# COUNTER1.net
KiCad netlist of a schematic drawn in EAGLE
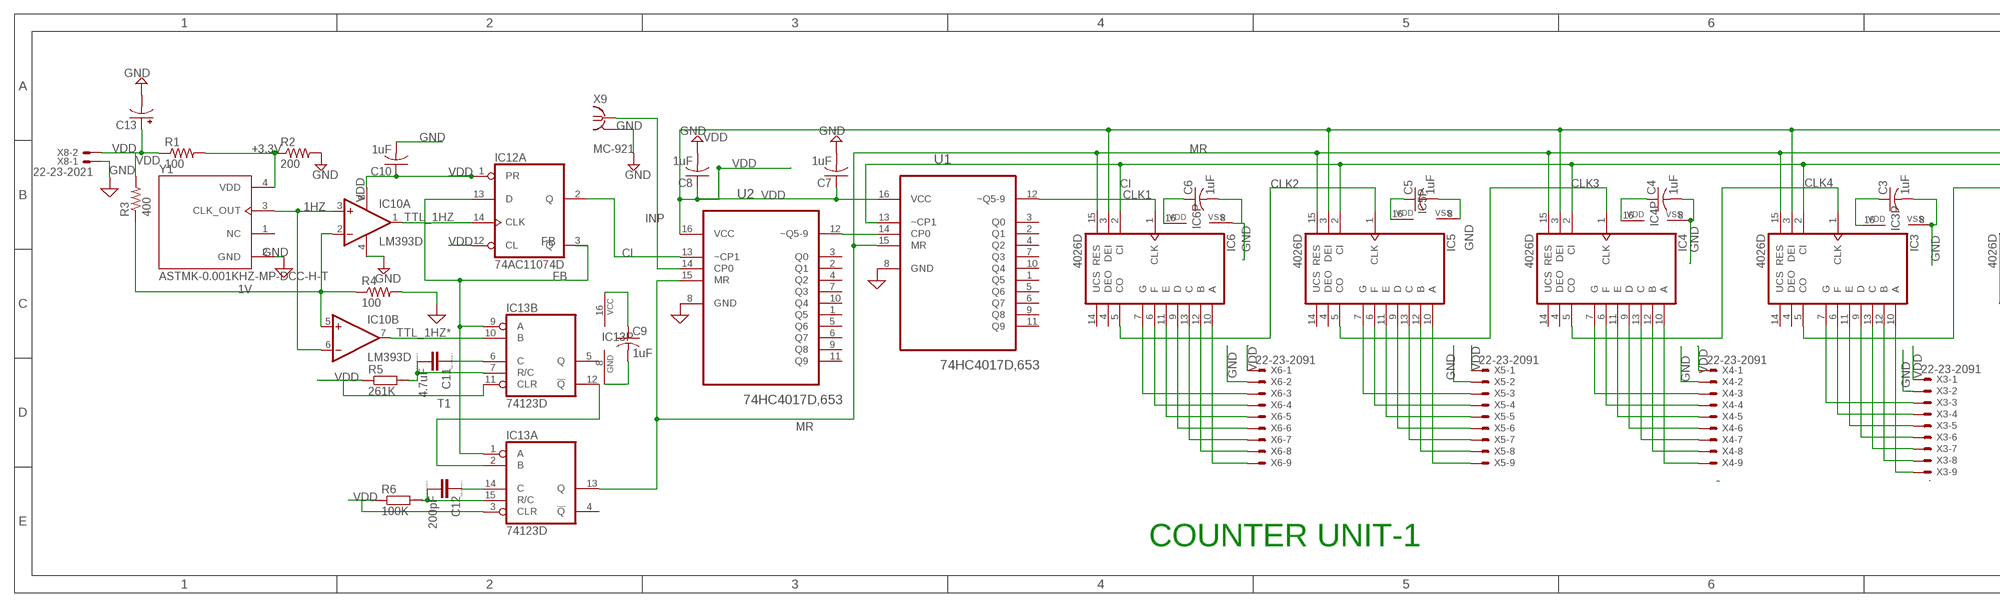
[diagram p0: schematic, sheet 1, part 1 of 2]
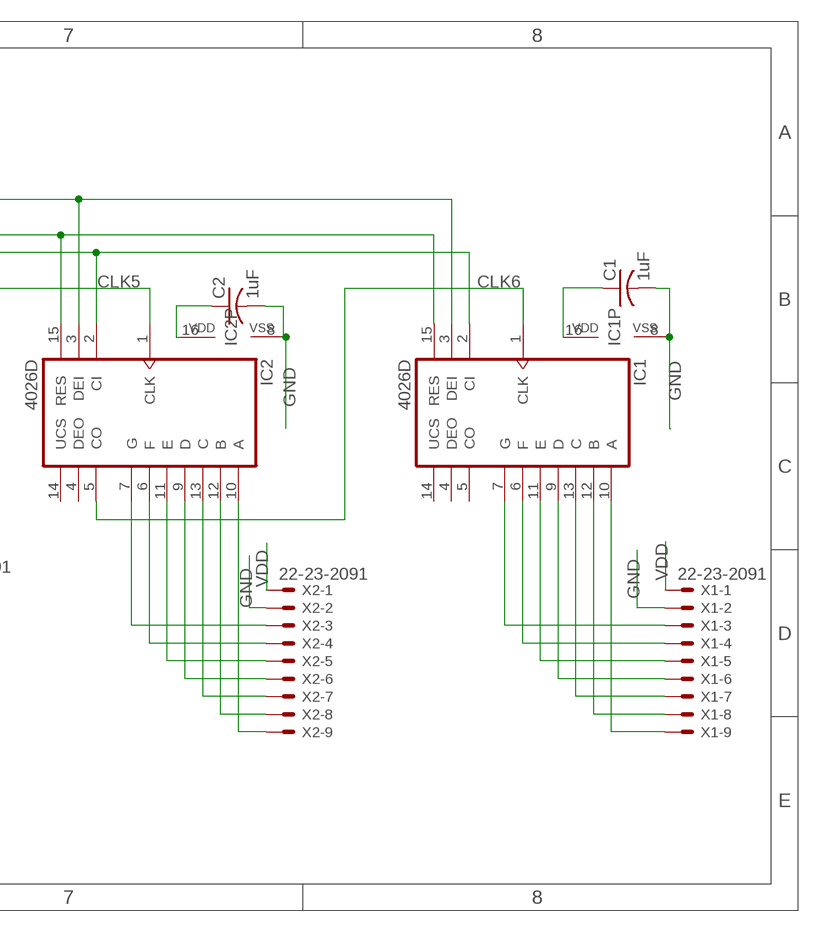
[diagram p1: schematic, sheet 1, part 2 of 2]

(export (version "E")
  (design (tool "Eeschema 10.0.6"))
  (components
    (comp (ref "C1")
      (value "1uF")
      (footprint "eagle-import:C0603")
      (libsource (lib "eagle-import") (part "C-USC0603"))
    )
    (comp (ref "C2")
      (value "1uF")
      (footprint "eagle-import:C0603")
      (libsource (lib "eagle-import") (part "C-USC0603"))
    )
    (comp (ref "C3")
      (value "1uF")
      (footprint "eagle-import:C0603")
      (libsource (lib "eagle-import") (part "C-USC0603"))
    )
    (comp (ref "C4")
      (value "1uF")
      (footprint "eagle-import:C0603")
      (libsource (lib "eagle-import") (part "C-USC0603"))
    )
    (comp (ref "C5")
      (value "1uF")
      (footprint "eagle-import:C0603")
      (libsource (lib "eagle-import") (part "C-USC0603"))
    )
    (comp (ref "C6")
      (value "1uF")
      (footprint "eagle-import:C0603")
      (libsource (lib "eagle-import") (part "C-USC0603"))
    )
    (comp (ref "C7")
      (value "1uF")
      (footprint "eagle-import:C0603")
      (libsource (lib "eagle-import") (part "C-USC0603"))
    )
    (comp (ref "C8")
      (value "1uF")
      (footprint "eagle-import:C0603")
      (libsource (lib "eagle-import") (part "C-USC0603"))
    )
    (comp (ref "C9")
      (value "1uF")
      (footprint "eagle-import:C0603")
      (libsource (lib "eagle-import") (part "C-USC0603"))
    )
    (comp (ref "C10")
      (value "1uF")
      (footprint "eagle-import:C0603")
      (libsource (lib "eagle-import") (part "C-USC0603"))
    )
    (comp (ref "C11")
      (value "4.7uF")
      (footprint "eagle-import:C0603")
      (libsource (lib "eagle-import") (part "CC0603"))
    )
    (comp (ref "C12")
      (value "200pF")
      (footprint "eagle-import:C0603")
      (libsource (lib "eagle-import") (part "CC0603"))
    )
    (comp (ref "C13")
      (value "CPOL-USE2-5")
      (footprint "eagle-import:E2-5")
      (libsource (lib "eagle-import") (part "CPOL-USE2-5"))
    )
    (comp (ref "IC1")
      (value "4026D")
      (footprint "eagle-import:SO16")
      (libsource (lib "eagle-import") (part "4026D"))
    )
    (comp (ref "IC2")
      (value "4026D")
      (footprint "eagle-import:SO16")
      (libsource (lib "eagle-import") (part "4026D"))
    )
    (comp (ref "IC3")
      (value "4026D")
      (footprint "eagle-import:SO16")
      (libsource (lib "eagle-import") (part "4026D"))
    )
    (comp (ref "IC4")
      (value "4026D")
      (footprint "eagle-import:SO16")
      (libsource (lib "eagle-import") (part "4026D"))
    )
    (comp (ref "IC5")
      (value "4026D")
      (footprint "eagle-import:SO16")
      (libsource (lib "eagle-import") (part "4026D"))
    )
    (comp (ref "IC6")
      (value "4026D")
      (footprint "eagle-import:SO16")
      (libsource (lib "eagle-import") (part "4026D"))
    )
    (comp (ref "IC10")
      (value "LM393D")
      (footprint "eagle-import:SO08")
      (libsource (lib "eagle-import") (part "LM393D"))
    )
    (comp (ref "IC12")
      (value "74AC11074D")
      (footprint "eagle-import:SO14")
      (libsource (lib "eagle-import") (part "74AC11074D"))
    )
    (comp (ref "IC13")
      (value "74123D")
      (footprint "eagle-import:SO16")
      (libsource (lib "eagle-import") (part "74123D"))
    )
    (comp (ref "R1")
      (value "100")
      (footprint "eagle-import:R0603")
      (libsource (lib "eagle-import") (part "R-US_R0603"))
    )
    (comp (ref "R2")
      (value "200")
      (footprint "eagle-import:R0603")
      (libsource (lib "eagle-import") (part "R-US_R0603"))
    )
    (comp (ref "R3")
      (value "400")
      (footprint "eagle-import:R0603")
      (libsource (lib "eagle-import") (part "R-US_R0603"))
    )
    (comp (ref "R4")
      (value "100")
      (footprint "eagle-import:R0603")
      (libsource (lib "eagle-import") (part "R-US_R0603"))
    )
    (comp (ref "R5")
      (value "261K")
      (footprint "eagle-import:R0603")
      (libsource (lib "eagle-import") (part "RR0603"))
    )
    (comp (ref "R6")
      (value "100K")
      (footprint "eagle-import:R0603")
      (libsource (lib "eagle-import") (part "RR0603"))
    )
    (comp (ref "U1")
      (value "74HC4017D,653")
      (footprint "eagle-import:SOIC127P600X175-16N")
      (fields (field (name "MF") "Nexperia USA Inc."))
      (libsource (lib "eagle-import") (part "74HC4017D,653"))
    )
    (comp (ref "U2")
      (value "74HC4017D,653")
      (footprint "eagle-import:SOIC127P600X175-16N")
      (fields (field (name "MF") "Nexperia USA Inc."))
      (libsource (lib "eagle-import") (part "74HC4017D,653"))
    )
    (comp (ref "X1")
      (value "22-23-2091")
      (footprint "eagle-import:22-23-2091")
      (fields (field (name "MF") "MOLEX"))
      (libsource (lib "eagle-import") (part "22-23-2091"))
    )
    (comp (ref "X2")
      (value "22-23-2091")
      (footprint "eagle-import:22-23-2091")
      (fields (field (name "MF") "MOLEX"))
      (libsource (lib "eagle-import") (part "22-23-2091"))
    )
    (comp (ref "X3")
      (value "22-23-2091")
      (footprint "eagle-import:22-23-2091")
      (fields (field (name "MF") "MOLEX"))
      (libsource (lib "eagle-import") (part "22-23-2091"))
    )
    (comp (ref "X4")
      (value "22-23-2091")
      (footprint "eagle-import:22-23-2091")
      (fields (field (name "MF") "MOLEX"))
      (libsource (lib "eagle-import") (part "22-23-2091"))
    )
    (comp (ref "X5")
      (value "22-23-2091")
      (footprint "eagle-import:22-23-2091")
      (fields (field (name "MF") "MOLEX"))
      (libsource (lib "eagle-import") (part "22-23-2091"))
    )
    (comp (ref "X6")
      (value "22-23-2091")
      (footprint "eagle-import:22-23-2091")
      (fields (field (name "MF") "MOLEX"))
      (libsource (lib "eagle-import") (part "22-23-2091"))
    )
    (comp (ref "X8")
      (value "22-23-2021")
      (footprint "eagle-import:22-23-2021")
      (fields (field (name "MF") "MOLEX"))
      (libsource (lib "eagle-import") (part "22-23-2021"))
    )
    (comp (ref "X9")
      (value "MC-921")
      (footprint "eagle-import:MC-921")
      (libsource (lib "eagle-import") (part "MC-921"))
    )
    (comp (ref "Y1")
      (value "ASTMK-0.001KHZ-MP-DCC-H-T")
      (footprint "eagle-import:OSC_ASTMK-0.001KHZ-MP-DCC-H-T")
      (fields (field (name "MF") "Abracon"))
      (libsource (lib "eagle-import") (part "ASTMK-0.001KHZ-MP-DCC-H-T"))
    )
  )
  (nets
    (net (code "1") (name "/+3.3V") (class "Default")
      (node (ref "R1") (pin "2") (pinfunction "2_2") (pintype "passive"))
      (node (ref "R2") (pin "1") (pinfunction "1_1") (pintype "passive"))
      (node (ref "Y1") (pin "4") (pinfunction "VDD_4") (pintype "power_in"))
    )
    (net (code "2") (name "/1HZ") (class "Default")
      (node (ref "IC10") (pin "3") (pinfunction "+IN_3") (pintype "input"))
      (node (ref "IC10") (pin "6") (pinfunction "-IN_6") (pintype "input"))
      (node (ref "Y1") (pin "3") (pinfunction "CLK_OUT_3") (pintype "output"))
    )
    (net (code "3") (name "/1V") (class "Default")
      (node (ref "IC10") (pin "2") (pinfunction "-IN_2") (pintype "input"))
      (node (ref "IC10") (pin "5") (pinfunction "+IN_5") (pintype "input"))
      (node (ref "R3") (pin "1") (pinfunction "1_1") (pintype "passive"))
      (node (ref "R4") (pin "1") (pinfunction "1_1") (pintype "passive"))
    )
    (net (code "4") (name "/CI") (class "Default")
      (node (ref "IC1") (pin "2") (pinfunction "CI_2") (pintype "input"))
      (node (ref "IC12") (pin "2") (pinfunction "Q_2") (pintype "output"))
      (node (ref "IC2") (pin "2") (pinfunction "CI_2") (pintype "input"))
      (node (ref "IC3") (pin "2") (pinfunction "CI_2") (pintype "input"))
      (node (ref "IC4") (pin "2") (pinfunction "CI_2") (pintype "input"))
      (node (ref "IC5") (pin "2") (pinfunction "CI_2") (pintype "input"))
      (node (ref "IC6") (pin "2") (pinfunction "CI_2") (pintype "input"))
      (node (ref "U1") (pin "13") (pinfunction "~{CP1}_13") (pintype "input"))
      (node (ref "U2") (pin "13") (pinfunction "~{CP1}_13") (pintype "input"))
    )
    (net (code "5") (name "/CLK1") (class "Default")
      (node (ref "IC6") (pin "1") (pinfunction "CLK_1") (pintype "input"))
      (node (ref "U1") (pin "12") (pinfunction "~{Q5-9}_12") (pintype "output"))
    )
    (net (code "6") (name "/CLK2") (class "Default")
      (node (ref "IC5") (pin "1") (pinfunction "CLK_1") (pintype "input"))
      (node (ref "IC6") (pin "5") (pinfunction "CO_5") (pintype "output"))
    )
    (net (code "7") (name "/CLK3") (class "Default")
      (node (ref "IC4") (pin "1") (pinfunction "CLK_1") (pintype "input"))
      (node (ref "IC5") (pin "5") (pinfunction "CO_5") (pintype "output"))
    )
    (net (code "8") (name "/CLK4") (class "Default")
      (node (ref "IC3") (pin "1") (pinfunction "CLK_1") (pintype "input"))
      (node (ref "IC4") (pin "5") (pinfunction "CO_5") (pintype "output"))
    )
    (net (code "9") (name "/CLK5") (class "Default")
      (node (ref "IC2") (pin "1") (pinfunction "CLK_1") (pintype "input"))
      (node (ref "IC3") (pin "5") (pinfunction "CO_5") (pintype "output"))
    )
    (net (code "10") (name "/CLK6") (class "Default")
      (node (ref "IC1") (pin "1") (pinfunction "CLK_1") (pintype "input"))
      (node (ref "IC2") (pin "5") (pinfunction "CO_5") (pintype "output"))
    )
    (net (code "11") (name "/FB") (class "Default")
      (node (ref "IC12") (pin "13") (pinfunction "D_13") (pintype "input"))
      (node (ref "IC12") (pin "3") (pinfunction "~{Q}_3") (pintype "output"))
      (node (ref "IC13") (pin "1") (pinfunction "A_1") (pintype "input"))
      (node (ref "IC13") (pin "9") (pinfunction "A_9") (pintype "input"))
    )
    (net (code "12") (name "/INP") (class "Default")
      (node (ref "U2") (pin "14") (pinfunction "CP0_14") (pintype "input"))
      (node (ref "X9") (pin "1") (pinfunction "1_1") (pintype "passive"))
    )
    (net (code "13") (name "/MR") (class "Default")
      (node (ref "IC1") (pin "15") (pinfunction "RES_15") (pintype "input"))
      (node (ref "IC13") (pin "13") (pinfunction "Q_13") (pintype "output"))
      (node (ref "IC2") (pin "15") (pinfunction "RES_15") (pintype "input"))
      (node (ref "IC3") (pin "15") (pinfunction "RES_15") (pintype "input"))
      (node (ref "IC4") (pin "15") (pinfunction "RES_15") (pintype "input"))
      (node (ref "IC5") (pin "15") (pinfunction "RES_15") (pintype "input"))
      (node (ref "IC6") (pin "15") (pinfunction "RES_15") (pintype "input"))
      (node (ref "U1") (pin "15") (pinfunction "MR_15") (pintype "input"))
      (node (ref "U2") (pin "15") (pinfunction "MR_15") (pintype "input"))
    )
    (net (code "14") (name "/RC1") (class "Default")
      (node (ref "C11") (pin "2") (pinfunction "2_2") (pintype "passive"))
      (node (ref "IC13") (pin "7") (pinfunction "R/C_7") (pintype "input"))
      (node (ref "R5") (pin "2") (pinfunction "2_2") (pintype "passive"))
    )
    (net (code "15") (name "/T1") (class "Default")
      (node (ref "IC13") (pin "12") (pinfunction "~{Q}_12") (pintype "output"))
      (node (ref "IC13") (pin "2") (pinfunction "B_2") (pintype "input"))
    )
    (net (code "16") (name "/TTL_1HZ") (class "Default")
      (node (ref "IC10") (pin "1") (pinfunction "OUT_1") (pintype "output"))
      (node (ref "IC12") (pin "14") (pinfunction "CLK_14") (pintype "input"))
    )
    (net (code "17") (name "/TTL_1HZ*") (class "Default")
      (node (ref "IC10") (pin "7") (pinfunction "OUT_7") (pintype "output"))
      (node (ref "IC13") (pin "10") (pinfunction "B_10") (pintype "input"))
    )
    (net (code "18") (name "/VDD") (class "Default")
      (node (ref "C1") (pin "1") (pinfunction "1_1") (pintype "passive"))
      (node (ref "C10") (pin "1") (pinfunction "1_1") (pintype "passive"))
      (node (ref "C13") (pin "+") (pinfunction "+_+") (pintype "passive"))
      (node (ref "C2") (pin "1") (pinfunction "1_1") (pintype "passive"))
      (node (ref "C3") (pin "1") (pinfunction "1_1") (pintype "passive"))
      (node (ref "C4") (pin "1") (pinfunction "1_1") (pintype "passive"))
      (node (ref "C5") (pin "1") (pinfunction "1_1") (pintype "passive"))
      (node (ref "C6") (pin "1") (pinfunction "1_1") (pintype "passive"))
      (node (ref "C7") (pin "1") (pinfunction "1_1") (pintype "passive"))
      (node (ref "C8") (pin "1") (pinfunction "1_1") (pintype "passive"))
      (node (ref "C9") (pin "1") (pinfunction "1_1") (pintype "passive"))
      (node (ref "IC1") (pin "16") (pinfunction "VDD_16") (pintype "power_in"))
      (node (ref "IC1") (pin "3") (pinfunction "DEI_3") (pintype "input"))
      (node (ref "IC10") (pin "8") (pinfunction "V+_8") (pintype "power_in"))
      (node (ref "IC12") (pin "1") (pinfunction "PR_1") (pintype "input"))
      (node (ref "IC12") (pin "12") (pinfunction "CL_12") (pintype "input"))
      (node (ref "IC13") (pin "16") (pinfunction "VCC_16") (pintype "power_in"))
      (node (ref "IC13") (pin "3") (pinfunction "CLR_3") (pintype "input"))
      (node (ref "IC2") (pin "16") (pinfunction "VDD_16") (pintype "power_in"))
      (node (ref "IC2") (pin "3") (pinfunction "DEI_3") (pintype "input"))
      (node (ref "IC3") (pin "16") (pinfunction "VDD_16") (pintype "power_in"))
      (node (ref "IC3") (pin "3") (pinfunction "DEI_3") (pintype "input"))
      (node (ref "IC4") (pin "16") (pinfunction "VDD_16") (pintype "power_in"))
      (node (ref "IC4") (pin "3") (pinfunction "DEI_3") (pintype "input"))
      (node (ref "IC5") (pin "16") (pinfunction "VDD_16") (pintype "power_in"))
      (node (ref "IC5") (pin "3") (pinfunction "DEI_3") (pintype "input"))
      (node (ref "IC6") (pin "16") (pinfunction "VDD_16") (pintype "power_in"))
      (node (ref "IC6") (pin "3") (pinfunction "DEI_3") (pintype "input"))
      (node (ref "R1") (pin "1") (pinfunction "1_1") (pintype "passive"))
      (node (ref "R3") (pin "2") (pinfunction "2_2") (pintype "passive"))
      (node (ref "R5") (pin "1") (pinfunction "1_1") (pintype "passive"))
      (node (ref "R6") (pin "1") (pinfunction "1_1") (pintype "passive"))
      (node (ref "U1") (pin "16") (pinfunction "VCC_16") (pintype "power_in"))
      (node (ref "U2") (pin "16") (pinfunction "VCC_16") (pintype "power_in"))
      (node (ref "X1") (pin "1") (pinfunction "S_1") (pintype "passive"))
      (node (ref "X2") (pin "1") (pinfunction "S_1") (pintype "passive"))
      (node (ref "X3") (pin "1") (pinfunction "S_1") (pintype "passive"))
      (node (ref "X4") (pin "1") (pinfunction "S_1") (pintype "passive"))
      (node (ref "X5") (pin "1") (pinfunction "S_1") (pintype "passive"))
      (node (ref "X6") (pin "1") (pinfunction "S_1") (pintype "passive"))
      (node (ref "X8") (pin "2") (pinfunction "S_2") (pintype "passive"))
    )
    (net (code "19") (name "GND") (class "Default")
      (node (ref "C1") (pin "2") (pinfunction "2_2") (pintype "passive"))
      (node (ref "C10") (pin "2") (pinfunction "2_2") (pintype "passive"))
      (node (ref "C13") (pin "-") (pinfunction "-_-") (pintype "passive"))
      (node (ref "C2") (pin "2") (pinfunction "2_2") (pintype "passive"))
      (node (ref "C3") (pin "2") (pinfunction "2_2") (pintype "passive"))
      (node (ref "C4") (pin "2") (pinfunction "2_2") (pintype "passive"))
      (node (ref "C5") (pin "2") (pinfunction "2_2") (pintype "passive"))
      (node (ref "C6") (pin "2") (pinfunction "2_2") (pintype "passive"))
      (node (ref "C7") (pin "2") (pinfunction "2_2") (pintype "passive"))
      (node (ref "C8") (pin "2") (pinfunction "2_2") (pintype "passive"))
      (node (ref "C9") (pin "2") (pinfunction "2_2") (pintype "passive"))
      (node (ref "IC1") (pin "8") (pinfunction "VSS_8") (pintype "power_in"))
      (node (ref "IC10") (pin "4") (pinfunction "V-_4") (pintype "power_in"))
      (node (ref "IC13") (pin "8") (pinfunction "GND_8") (pintype "power_in"))
      (node (ref "IC2") (pin "8") (pinfunction "VSS_8") (pintype "power_in"))
      (node (ref "IC3") (pin "8") (pinfunction "VSS_8") (pintype "power_in"))
      (node (ref "IC4") (pin "8") (pinfunction "VSS_8") (pintype "power_in"))
      (node (ref "IC5") (pin "8") (pinfunction "VSS_8") (pintype "power_in"))
      (node (ref "IC6") (pin "8") (pinfunction "VSS_8") (pintype "power_in"))
      (node (ref "R2") (pin "2") (pinfunction "2_2") (pintype "passive"))
      (node (ref "R4") (pin "2") (pinfunction "2_2") (pintype "passive"))
      (node (ref "U1") (pin "8") (pinfunction "GND_8") (pintype "passive"))
      (node (ref "U2") (pin "8") (pinfunction "GND_8") (pintype "passive"))
      (node (ref "X1") (pin "2") (pinfunction "S_2") (pintype "passive"))
      (node (ref "X2") (pin "2") (pinfunction "S_2") (pintype "passive"))
      (node (ref "X3") (pin "2") (pinfunction "S_2") (pintype "passive"))
      (node (ref "X4") (pin "2") (pinfunction "S_2") (pintype "passive"))
      (node (ref "X5") (pin "2") (pinfunction "S_2") (pintype "passive"))
      (node (ref "X6") (pin "2") (pinfunction "S_2") (pintype "passive"))
      (node (ref "X8") (pin "1") (pinfunction "S_1") (pintype "passive"))
      (node (ref "X9") (pin "2@1") (pinfunction "GND_2@1") (pintype "passive"))
      (node (ref "X9") (pin "2@2") (pinfunction "GND_2@2") (pintype "passive"))
      (node (ref "Y1") (pin "2") (pinfunction "GND_2") (pintype "power_in"))
    )
    (net (code "20") (name "Net-(IC1A-A)") (class "Default")
      (node (ref "IC1") (pin "10") (pinfunction "A_10") (pintype "output"))
      (node (ref "X1") (pin "9") (pinfunction "S_9") (pintype "passive"))
    )
    (net (code "21") (name "Net-(IC1A-B)") (class "Default")
      (node (ref "IC1") (pin "12") (pinfunction "B_12") (pintype "output"))
      (node (ref "X1") (pin "8") (pinfunction "S_8") (pintype "passive"))
    )
    (net (code "22") (name "Net-(IC1A-C)") (class "Default")
      (node (ref "IC1") (pin "13") (pinfunction "C_13") (pintype "output"))
      (node (ref "X1") (pin "7") (pinfunction "S_7") (pintype "passive"))
    )
    (net (code "23") (name "Net-(IC1A-D)") (class "Default")
      (node (ref "IC1") (pin "9") (pinfunction "D_9") (pintype "output"))
      (node (ref "X1") (pin "6") (pinfunction "S_6") (pintype "passive"))
    )
    (net (code "24") (name "Net-(IC1A-E)") (class "Default")
      (node (ref "IC1") (pin "11") (pinfunction "E_11") (pintype "output"))
      (node (ref "X1") (pin "5") (pinfunction "S_5") (pintype "passive"))
    )
    (net (code "25") (name "Net-(IC1A-F)") (class "Default")
      (node (ref "IC1") (pin "6") (pinfunction "F_6") (pintype "output"))
      (node (ref "X1") (pin "4") (pinfunction "S_4") (pintype "passive"))
    )
    (net (code "26") (name "Net-(IC1A-G)") (class "Default")
      (node (ref "IC1") (pin "7") (pinfunction "G_7") (pintype "output"))
      (node (ref "X1") (pin "3") (pinfunction "S_3") (pintype "passive"))
    )
    (net (code "27") (name "Net-(IC2A-A)") (class "Default")
      (node (ref "IC2") (pin "10") (pinfunction "A_10") (pintype "output"))
      (node (ref "X2") (pin "9") (pinfunction "S_9") (pintype "passive"))
    )
    (net (code "28") (name "Net-(IC2A-B)") (class "Default")
      (node (ref "IC2") (pin "12") (pinfunction "B_12") (pintype "output"))
      (node (ref "X2") (pin "8") (pinfunction "S_8") (pintype "passive"))
    )
    (net (code "29") (name "Net-(IC2A-C)") (class "Default")
      (node (ref "IC2") (pin "13") (pinfunction "C_13") (pintype "output"))
      (node (ref "X2") (pin "7") (pinfunction "S_7") (pintype "passive"))
    )
    (net (code "30") (name "Net-(IC2A-D)") (class "Default")
      (node (ref "IC2") (pin "9") (pinfunction "D_9") (pintype "output"))
      (node (ref "X2") (pin "6") (pinfunction "S_6") (pintype "passive"))
    )
    (net (code "31") (name "Net-(IC2A-E)") (class "Default")
      (node (ref "IC2") (pin "11") (pinfunction "E_11") (pintype "output"))
      (node (ref "X2") (pin "5") (pinfunction "S_5") (pintype "passive"))
    )
    (net (code "32") (name "Net-(IC2A-F)") (class "Default")
      (node (ref "IC2") (pin "6") (pinfunction "F_6") (pintype "output"))
      (node (ref "X2") (pin "4") (pinfunction "S_4") (pintype "passive"))
    )
    (net (code "33") (name "Net-(IC2A-G)") (class "Default")
      (node (ref "IC2") (pin "7") (pinfunction "G_7") (pintype "output"))
      (node (ref "X2") (pin "3") (pinfunction "S_3") (pintype "passive"))
    )
    (net (code "34") (name "Net-(IC3A-A)") (class "Default")
      (node (ref "IC3") (pin "10") (pinfunction "A_10") (pintype "output"))
      (node (ref "X3") (pin "9") (pinfunction "S_9") (pintype "passive"))
    )
    (net (code "35") (name "Net-(IC3A-B)") (class "Default")
      (node (ref "IC3") (pin "12") (pinfunction "B_12") (pintype "output"))
      (node (ref "X3") (pin "8") (pinfunction "S_8") (pintype "passive"))
    )
    (net (code "36") (name "Net-(IC3A-C)") (class "Default")
      (node (ref "IC3") (pin "13") (pinfunction "C_13") (pintype "output"))
      (node (ref "X3") (pin "7") (pinfunction "S_7") (pintype "passive"))
    )
    (net (code "37") (name "Net-(IC3A-D)") (class "Default")
      (node (ref "IC3") (pin "9") (pinfunction "D_9") (pintype "output"))
      (node (ref "X3") (pin "6") (pinfunction "S_6") (pintype "passive"))
    )
    (net (code "38") (name "Net-(IC3A-E)") (class "Default")
      (node (ref "IC3") (pin "11") (pinfunction "E_11") (pintype "output"))
      (node (ref "X3") (pin "5") (pinfunction "S_5") (pintype "passive"))
    )
    (net (code "39") (name "Net-(IC3A-F)") (class "Default")
      (node (ref "IC3") (pin "6") (pinfunction "F_6") (pintype "output"))
      (node (ref "X3") (pin "4") (pinfunction "S_4") (pintype "passive"))
    )
    (net (code "40") (name "Net-(IC3A-G)") (class "Default")
      (node (ref "IC3") (pin "7") (pinfunction "G_7") (pintype "output"))
      (node (ref "X3") (pin "3") (pinfunction "S_3") (pintype "passive"))
    )
    (net (code "41") (name "Net-(IC4A-A)") (class "Default")
      (node (ref "IC4") (pin "10") (pinfunction "A_10") (pintype "output"))
      (node (ref "X4") (pin "9") (pinfunction "S_9") (pintype "passive"))
    )
    (net (code "42") (name "Net-(IC4A-B)") (class "Default")
      (node (ref "IC4") (pin "12") (pinfunction "B_12") (pintype "output"))
      (node (ref "X4") (pin "8") (pinfunction "S_8") (pintype "passive"))
    )
    (net (code "43") (name "Net-(IC4A-C)") (class "Default")
      (node (ref "IC4") (pin "13") (pinfunction "C_13") (pintype "output"))
      (node (ref "X4") (pin "7") (pinfunction "S_7") (pintype "passive"))
    )
    (net (code "44") (name "Net-(IC4A-D)") (class "Default")
      (node (ref "IC4") (pin "9") (pinfunction "D_9") (pintype "output"))
      (node (ref "X4") (pin "6") (pinfunction "S_6") (pintype "passive"))
    )
    (net (code "45") (name "Net-(IC4A-E)") (class "Default")
      (node (ref "IC4") (pin "11") (pinfunction "E_11") (pintype "output"))
      (node (ref "X4") (pin "5") (pinfunction "S_5") (pintype "passive"))
    )
    (net (code "46") (name "Net-(IC4A-F)") (class "Default")
      (node (ref "IC4") (pin "6") (pinfunction "F_6") (pintype "output"))
      (node (ref "X4") (pin "4") (pinfunction "S_4") (pintype "passive"))
    )
    (net (code "47") (name "Net-(IC4A-G)") (class "Default")
      (node (ref "IC4") (pin "7") (pinfunction "G_7") (pintype "output"))
      (node (ref "X4") (pin "3") (pinfunction "S_3") (pintype "passive"))
    )
    (net (code "48") (name "Net-(IC5A-A)") (class "Default")
      (node (ref "IC5") (pin "10") (pinfunction "A_10") (pintype "output"))
      (node (ref "X5") (pin "9") (pinfunction "S_9") (pintype "passive"))
    )
    (net (code "49") (name "Net-(IC5A-B)") (class "Default")
      (node (ref "IC5") (pin "12") (pinfunction "B_12") (pintype "output"))
      (node (ref "X5") (pin "8") (pinfunction "S_8") (pintype "passive"))
    )
    (net (code "50") (name "Net-(IC5A-C)") (class "Default")
      (node (ref "IC5") (pin "13") (pinfunction "C_13") (pintype "output"))
      (node (ref "X5") (pin "7") (pinfunction "S_7") (pintype "passive"))
    )
    (net (code "51") (name "Net-(IC5A-D)") (class "Default")
      (node (ref "IC5") (pin "9") (pinfunction "D_9") (pintype "output"))
      (node (ref "X5") (pin "6") (pinfunction "S_6") (pintype "passive"))
    )
    (net (code "52") (name "Net-(IC5A-E)") (class "Default")
      (node (ref "IC5") (pin "11") (pinfunction "E_11") (pintype "output"))
      (node (ref "X5") (pin "5") (pinfunction "S_5") (pintype "passive"))
    )
    (net (code "53") (name "Net-(IC5A-F)") (class "Default")
      (node (ref "IC5") (pin "6") (pinfunction "F_6") (pintype "output"))
      (node (ref "X5") (pin "4") (pinfunction "S_4") (pintype "passive"))
    )
    (net (code "54") (name "Net-(IC5A-G)") (class "Default")
      (node (ref "IC5") (pin "7") (pinfunction "G_7") (pintype "output"))
      (node (ref "X5") (pin "3") (pinfunction "S_3") (pintype "passive"))
    )
    (net (code "55") (name "Net-(IC6A-A)") (class "Default")
      (node (ref "IC6") (pin "10") (pinfunction "A_10") (pintype "output"))
      (node (ref "X6") (pin "9") (pinfunction "S_9") (pintype "passive"))
    )
    (net (code "56") (name "Net-(IC6A-B)") (class "Default")
      (node (ref "IC6") (pin "12") (pinfunction "B_12") (pintype "output"))
      (node (ref "X6") (pin "8") (pinfunction "S_8") (pintype "passive"))
    )
    (net (code "57") (name "Net-(IC6A-C)") (class "Default")
      (node (ref "IC6") (pin "13") (pinfunction "C_13") (pintype "output"))
      (node (ref "X6") (pin "7") (pinfunction "S_7") (pintype "passive"))
    )
    (net (code "58") (name "Net-(IC6A-D)") (class "Default")
      (node (ref "IC6") (pin "9") (pinfunction "D_9") (pintype "output"))
      (node (ref "X6") (pin "6") (pinfunction "S_6") (pintype "passive"))
    )
    (net (code "59") (name "Net-(IC6A-E)") (class "Default")
      (node (ref "IC6") (pin "11") (pinfunction "E_11") (pintype "output"))
      (node (ref "X6") (pin "5") (pinfunction "S_5") (pintype "passive"))
    )
    (net (code "60") (name "Net-(IC6A-F)") (class "Default")
      (node (ref "IC6") (pin "6") (pinfunction "F_6") (pintype "output"))
      (node (ref "X6") (pin "4") (pinfunction "S_4") (pintype "passive"))
    )
    (net (code "61") (name "Net-(IC6A-G)") (class "Default")
      (node (ref "IC6") (pin "7") (pinfunction "G_7") (pintype "output"))
      (node (ref "X6") (pin "3") (pinfunction "S_3") (pintype "passive"))
    )
    (net (code "62") (name "Net-(IC13A-C)") (class "Default")
      (node (ref "C12") (pin "1") (pinfunction "1_1") (pintype "passive"))
      (node (ref "IC13") (pin "14") (pinfunction "C_14") (pintype "input"))
    )
    (net (code "63") (name "Net-(IC13A-R{slash}C)") (class "Default")
      (node (ref "C12") (pin "2") (pinfunction "2_2") (pintype "passive"))
      (node (ref "IC13") (pin "15") (pinfunction "R/C_15") (pintype "input"))
      (node (ref "R6") (pin "2") (pinfunction "2_2") (pintype "passive"))
    )
    (net (code "64") (name "Net-(IC13B-C)") (class "Default")
      (node (ref "C11") (pin "1") (pinfunction "1_1") (pintype "passive"))
      (node (ref "IC13") (pin "6") (pinfunction "C_6") (pintype "input"))
    )
    (net (code "65") (name "Net-(U1-CP0)") (class "Default")
      (node (ref "U1") (pin "14") (pinfunction "CP0_14") (pintype "input"))
      (node (ref "U2") (pin "12") (pinfunction "~{Q5-9}_12") (pintype "output"))
    )
    (net (code "66") (name "unconnected-(IC1A-CO-Pad5)") (class "Default")
      (node (ref "IC1") (pin "5") (pinfunction "CO_5") (pintype "output"))
    )
    (net (code "67") (name "unconnected-(IC1A-DEO-Pad4)") (class "Default")
      (node (ref "IC1") (pin "4") (pinfunction "DEO_4") (pintype "output"))
    )
    (net (code "68") (name "unconnected-(IC1A-UCS-Pad14)") (class "Default")
      (node (ref "IC1") (pin "14") (pinfunction "UCS_14") (pintype "output"))
    )
    (net (code "69") (name "unconnected-(IC2A-DEO-Pad4)") (class "Default")
      (node (ref "IC2") (pin "4") (pinfunction "DEO_4") (pintype "output"))
    )
    (net (code "70") (name "unconnected-(IC2A-UCS-Pad14)") (class "Default")
      (node (ref "IC2") (pin "14") (pinfunction "UCS_14") (pintype "output"))
    )
    (net (code "71") (name "unconnected-(IC3A-DEO-Pad4)") (class "Default")
      (node (ref "IC3") (pin "4") (pinfunction "DEO_4") (pintype "output"))
    )
    (net (code "72") (name "unconnected-(IC3A-UCS-Pad14)") (class "Default")
      (node (ref "IC3") (pin "14") (pinfunction "UCS_14") (pintype "output"))
    )
    (net (code "73") (name "unconnected-(IC4A-DEO-Pad4)") (class "Default")
      (node (ref "IC4") (pin "4") (pinfunction "DEO_4") (pintype "output"))
    )
    (net (code "74") (name "unconnected-(IC4A-UCS-Pad14)") (class "Default")
      (node (ref "IC4") (pin "14") (pinfunction "UCS_14") (pintype "output"))
    )
    (net (code "75") (name "unconnected-(IC5A-DEO-Pad4)") (class "Default")
      (node (ref "IC5") (pin "4") (pinfunction "DEO_4") (pintype "output"))
    )
    (net (code "76") (name "unconnected-(IC5A-UCS-Pad14)") (class "Default")
      (node (ref "IC5") (pin "14") (pinfunction "UCS_14") (pintype "output"))
    )
    (net (code "77") (name "unconnected-(IC6A-DEO-Pad4)") (class "Default")
      (node (ref "IC6") (pin "4") (pinfunction "DEO_4") (pintype "output"))
    )
    (net (code "78") (name "unconnected-(IC6A-UCS-Pad14)") (class "Default")
      (node (ref "IC6") (pin "14") (pinfunction "UCS_14") (pintype "output"))
    )
    (net (code "79") (name "unconnected-(IC13A-~{Q}-Pad4)") (class "Default")
      (node (ref "IC13") (pin "4") (pinfunction "~{Q}_4") (pintype "output"))
    )
    (net (code "80") (name "unconnected-(IC13B-CLR-Pad11)") (class "Default")
      (node (ref "IC13") (pin "11") (pinfunction "CLR_11") (pintype "input"))
    )
    (net (code "81") (name "unconnected-(IC13B-Q-Pad5)") (class "Default")
      (node (ref "IC13") (pin "5") (pinfunction "Q_5") (pintype "output"))
    )
    (net (code "82") (name "unconnected-(U1-Q0-Pad3)") (class "Default")
      (node (ref "U1") (pin "3") (pinfunction "Q0_3") (pintype "output"))
    )
    (net (code "83") (name "unconnected-(U1-Q1-Pad2)") (class "Default")
      (node (ref "U1") (pin "2") (pinfunction "Q1_2") (pintype "output"))
    )
    (net (code "84") (name "unconnected-(U1-Q2-Pad4)") (class "Default")
      (node (ref "U1") (pin "4") (pinfunction "Q2_4") (pintype "output"))
    )
    (net (code "85") (name "unconnected-(U1-Q3-Pad7)") (class "Default")
      (node (ref "U1") (pin "7") (pinfunction "Q3_7") (pintype "output"))
    )
    (net (code "86") (name "unconnected-(U1-Q4-Pad10)") (class "Default")
      (node (ref "U1") (pin "10") (pinfunction "Q4_10") (pintype "output"))
    )
    (net (code "87") (name "unconnected-(U1-Q5-Pad1)") (class "Default")
      (node (ref "U1") (pin "1") (pinfunction "Q5_1") (pintype "output"))
    )
    (net (code "88") (name "unconnected-(U1-Q6-Pad5)") (class "Default")
      (node (ref "U1") (pin "5") (pinfunction "Q6_5") (pintype "output"))
    )
    (net (code "89") (name "unconnected-(U1-Q7-Pad6)") (class "Default")
      (node (ref "U1") (pin "6") (pinfunction "Q7_6") (pintype "output"))
    )
    (net (code "90") (name "unconnected-(U1-Q8-Pad9)") (class "Default")
      (node (ref "U1") (pin "9") (pinfunction "Q8_9") (pintype "output"))
    )
    (net (code "91") (name "unconnected-(U1-Q9-Pad11)") (class "Default")
      (node (ref "U1") (pin "11") (pinfunction "Q9_11") (pintype "output"))
    )
    (net (code "92") (name "unconnected-(U2-Q0-Pad3)") (class "Default")
      (node (ref "U2") (pin "3") (pinfunction "Q0_3") (pintype "output"))
    )
    (net (code "93") (name "unconnected-(U2-Q1-Pad2)") (class "Default")
      (node (ref "U2") (pin "2") (pinfunction "Q1_2") (pintype "output"))
    )
    (net (code "94") (name "unconnected-(U2-Q2-Pad4)") (class "Default")
      (node (ref "U2") (pin "4") (pinfunction "Q2_4") (pintype "output"))
    )
    (net (code "95") (name "unconnected-(U2-Q3-Pad7)") (class "Default")
      (node (ref "U2") (pin "7") (pinfunction "Q3_7") (pintype "output"))
    )
    (net (code "96") (name "unconnected-(U2-Q4-Pad10)") (class "Default")
      (node (ref "U2") (pin "10") (pinfunction "Q4_10") (pintype "output"))
    )
    (net (code "97") (name "unconnected-(U2-Q5-Pad1)") (class "Default")
      (node (ref "U2") (pin "1") (pinfunction "Q5_1") (pintype "output"))
    )
    (net (code "98") (name "unconnected-(U2-Q6-Pad5)") (class "Default")
      (node (ref "U2") (pin "5") (pinfunction "Q6_5") (pintype "output"))
    )
    (net (code "99") (name "unconnected-(U2-Q7-Pad6)") (class "Default")
      (node (ref "U2") (pin "6") (pinfunction "Q7_6") (pintype "output"))
    )
    (net (code "100") (name "unconnected-(U2-Q8-Pad9)") (class "Default")
      (node (ref "U2") (pin "9") (pinfunction "Q8_9") (pintype "output"))
    )
    (net (code "101") (name "unconnected-(U2-Q9-Pad11)") (class "Default")
      (node (ref "U2") (pin "11") (pinfunction "Q9_11") (pintype "output"))
    )
    (net (code "102") (name "unconnected-(Y1-NC-Pad1)") (class "Default")
      (node (ref "Y1") (pin "1") (pinfunction "NC_1") (pintype "no_connect"))
    )
  )
)
